# M_J_ext_disp.net
KiCad netlist of a schematic drawn in EAGLE
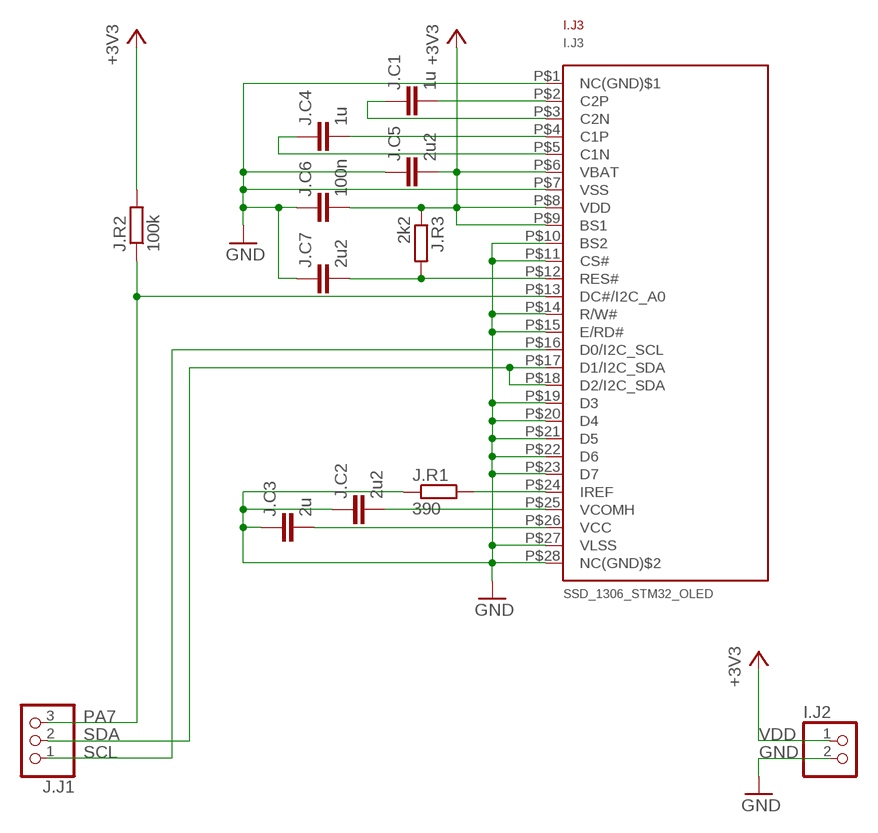
[diagram p0: schematic, sheet 1]

(export (version "E")
  (design (tool "Eeschema 10.0.6"))
  (components
    (comp (ref "I.J2")
      (value "PINHD-1X2")
      (footprint "eagle-import:1X02")
      (libsource (lib "eagle-import") (part "PINHD-1X2"))
    )
    (comp (ref "I.J3")
      (value "SSD_1306_STM32_OLED")
      (footprint "eagle-import:SSD_1306_STM32_OLED")
      (libsource (lib "eagle-import") (part "SSD_1306_STM32_OLED"))
    )
    (comp (ref "J.C1")
      (value "1u")
      (footprint "eagle-import:C0603")
      (libsource (lib "eagle-import") (part "C-EUC0603"))
    )
    (comp (ref "J.C2")
      (value "2u2")
      (footprint "eagle-import:C0603")
      (libsource (lib "eagle-import") (part "C-EUC0603"))
    )
    (comp (ref "J.C3")
      (value "2u")
      (footprint "eagle-import:C0603")
      (libsource (lib "eagle-import") (part "C-EUC0603"))
    )
    (comp (ref "J.C4")
      (value "1u")
      (footprint "eagle-import:C0603")
      (libsource (lib "eagle-import") (part "C-EUC0603"))
    )
    (comp (ref "J.C5")
      (value "2u2")
      (footprint "eagle-import:C0603")
      (libsource (lib "eagle-import") (part "C-EUC0603"))
    )
    (comp (ref "J.C6")
      (value "100n")
      (footprint "eagle-import:C0603")
      (libsource (lib "eagle-import") (part "C-EUC0603"))
    )
    (comp (ref "J.C7")
      (value "2u2")
      (footprint "eagle-import:C0603")
      (libsource (lib "eagle-import") (part "C-EUC0603"))
    )
    (comp (ref "J.J1")
      (value "PINHD-1X3")
      (footprint "eagle-import:1X03")
      (libsource (lib "eagle-import") (part "PINHD-1X3"))
    )
    (comp (ref "J.R1")
      (value "390")
      (footprint "eagle-import:R0603")
      (libsource (lib "eagle-import") (part "R-EU_R0603"))
    )
    (comp (ref "J.R2")
      (value "100k")
      (footprint "eagle-import:R0603")
      (libsource (lib "eagle-import") (part "R-EU_R0603"))
    )
    (comp (ref "J.R3")
      (value "2k2")
      (footprint "eagle-import:R0603")
      (libsource (lib "eagle-import") (part "R-EU_R0603"))
    )
  )
  (nets
    (net (code "1") (name "+3V3") (class "Default")
      (node (ref "I.J2") (pin "1") (pinfunction "1_1") (pintype "passive"))
      (node (ref "I.J3") (pin "P$6") (pinfunction "VBAT_P$6") (pintype "input"))
      (node (ref "I.J3") (pin "P$8") (pinfunction "VDD_P$8") (pintype "power_in"))
      (node (ref "I.J3") (pin "P$9") (pinfunction "BS1_P$9") (pintype "input"))
      (node (ref "J.C5") (pin "2") (pinfunction "2_2") (pintype "passive"))
      (node (ref "J.C6") (pin "2") (pinfunction "2_2") (pintype "passive"))
      (node (ref "J.R2") (pin "2") (pinfunction "2_2") (pintype "passive"))
      (node (ref "J.R3") (pin "1") (pinfunction "1_1") (pintype "passive"))
    )
    (net (code "2") (name "/PA7") (class "Default")
      (node (ref "I.J3") (pin "P$13") (pinfunction "DC#/I2C_A0_P$13") (pintype "input"))
      (node (ref "J.J1") (pin "3") (pinfunction "3_3") (pintype "passive"))
      (node (ref "J.R2") (pin "1") (pinfunction "1_1") (pintype "passive"))
    )
    (net (code "3") (name "/SCL") (class "Default")
      (node (ref "I.J3") (pin "P$16") (pinfunction "D0/I2C_SCL_P$16") (pintype "bidirectional"))
      (node (ref "J.J1") (pin "1") (pinfunction "1_1") (pintype "passive"))
    )
    (net (code "4") (name "/SDA") (class "Default")
      (node (ref "I.J3") (pin "P$17") (pinfunction "D1/I2C_SDA_P$17") (pintype "bidirectional"))
      (node (ref "I.J3") (pin "P$18") (pinfunction "D2/I2C_SDA_P$18") (pintype "bidirectional"))
      (node (ref "J.J1") (pin "2") (pinfunction "2_2") (pintype "passive"))
    )
    (net (code "5") (name "GND") (class "Default")
      (node (ref "I.J2") (pin "2") (pinfunction "2_2") (pintype "passive"))
      (node (ref "I.J3") (pin "P$1") (pinfunction "NC(GND)$1_P$1") (pintype "input"))
      (node (ref "I.J3") (pin "P$10") (pinfunction "BS2_P$10") (pintype "input"))
      (node (ref "I.J3") (pin "P$11") (pinfunction "CS#_P$11") (pintype "input"))
      (node (ref "I.J3") (pin "P$14") (pinfunction "R/W#_P$14") (pintype "input"))
      (node (ref "I.J3") (pin "P$15") (pinfunction "E/RD#_P$15") (pintype "input"))
      (node (ref "I.J3") (pin "P$19") (pinfunction "D3_P$19") (pintype "bidirectional"))
      (node (ref "I.J3") (pin "P$20") (pinfunction "D4_P$20") (pintype "bidirectional"))
      (node (ref "I.J3") (pin "P$21") (pinfunction "D5_P$21") (pintype "bidirectional"))
      (node (ref "I.J3") (pin "P$22") (pinfunction "D6_P$22") (pintype "bidirectional"))
      (node (ref "I.J3") (pin "P$23") (pinfunction "D7_P$23") (pintype "bidirectional"))
      (node (ref "I.J3") (pin "P$27") (pinfunction "VLSS_P$27") (pintype "power_in"))
      (node (ref "I.J3") (pin "P$28") (pinfunction "NC(GND)$2_P$28") (pintype "input"))
      (node (ref "I.J3") (pin "P$7") (pinfunction "VSS_P$7") (pintype "power_in"))
      (node (ref "J.C2") (pin "1") (pinfunction "1_1") (pintype "passive"))
      (node (ref "J.C3") (pin "1") (pinfunction "1_1") (pintype "passive"))
      (node (ref "J.C5") (pin "1") (pinfunction "1_1") (pintype "passive"))
      (node (ref "J.C6") (pin "1") (pinfunction "1_1") (pintype "passive"))
      (node (ref "J.C7") (pin "1") (pinfunction "1_1") (pintype "passive"))
      (node (ref "J.R1") (pin "1") (pinfunction "1_1") (pintype "passive"))
    )
    (net (code "6") (name "Net-(I.J3-C1N)") (class "Default")
      (node (ref "I.J3") (pin "P$5") (pinfunction "C1N_P$5") (pintype "input"))
      (node (ref "J.C4") (pin "1") (pinfunction "1_1") (pintype "passive"))
    )
    (net (code "7") (name "Net-(I.J3-C1P)") (class "Default")
      (node (ref "I.J3") (pin "P$4") (pinfunction "C1P_P$4") (pintype "input"))
      (node (ref "J.C4") (pin "2") (pinfunction "2_2") (pintype "passive"))
    )
    (net (code "8") (name "Net-(I.J3-C2N)") (class "Default")
      (node (ref "I.J3") (pin "P$3") (pinfunction "C2N_P$3") (pintype "input"))
      (node (ref "J.C1") (pin "1") (pinfunction "1_1") (pintype "passive"))
    )
    (net (code "9") (name "Net-(I.J3-C2P)") (class "Default")
      (node (ref "I.J3") (pin "P$2") (pinfunction "C2P_P$2") (pintype "input"))
      (node (ref "J.C1") (pin "2") (pinfunction "2_2") (pintype "passive"))
    )
    (net (code "10") (name "Net-(I.J3-IREF)") (class "Default")
      (node (ref "I.J3") (pin "P$24") (pinfunction "IREF_P$24") (pintype "input"))
      (node (ref "J.R1") (pin "2") (pinfunction "2_2") (pintype "passive"))
    )
    (net (code "11") (name "Net-(I.J3-RES#)") (class "Default")
      (node (ref "I.J3") (pin "P$12") (pinfunction "RES#_P$12") (pintype "input"))
      (node (ref "J.C7") (pin "2") (pinfunction "2_2") (pintype "passive"))
      (node (ref "J.R3") (pin "2") (pinfunction "2_2") (pintype "passive"))
    )
    (net (code "12") (name "Net-(I.J3-VCC)") (class "Default")
      (node (ref "I.J3") (pin "P$26") (pinfunction "VCC_P$26") (pintype "power_in"))
      (node (ref "J.C3") (pin "2") (pinfunction "2_2") (pintype "passive"))
    )
    (net (code "13") (name "Net-(I.J3-VCOMH)") (class "Default")
      (node (ref "I.J3") (pin "P$25") (pinfunction "VCOMH_P$25") (pintype "output"))
      (node (ref "J.C2") (pin "2") (pinfunction "2_2") (pintype "passive"))
    )
  )
)
